# powerdist2.net
KiCad netlist of a schematic drawn in EAGLE
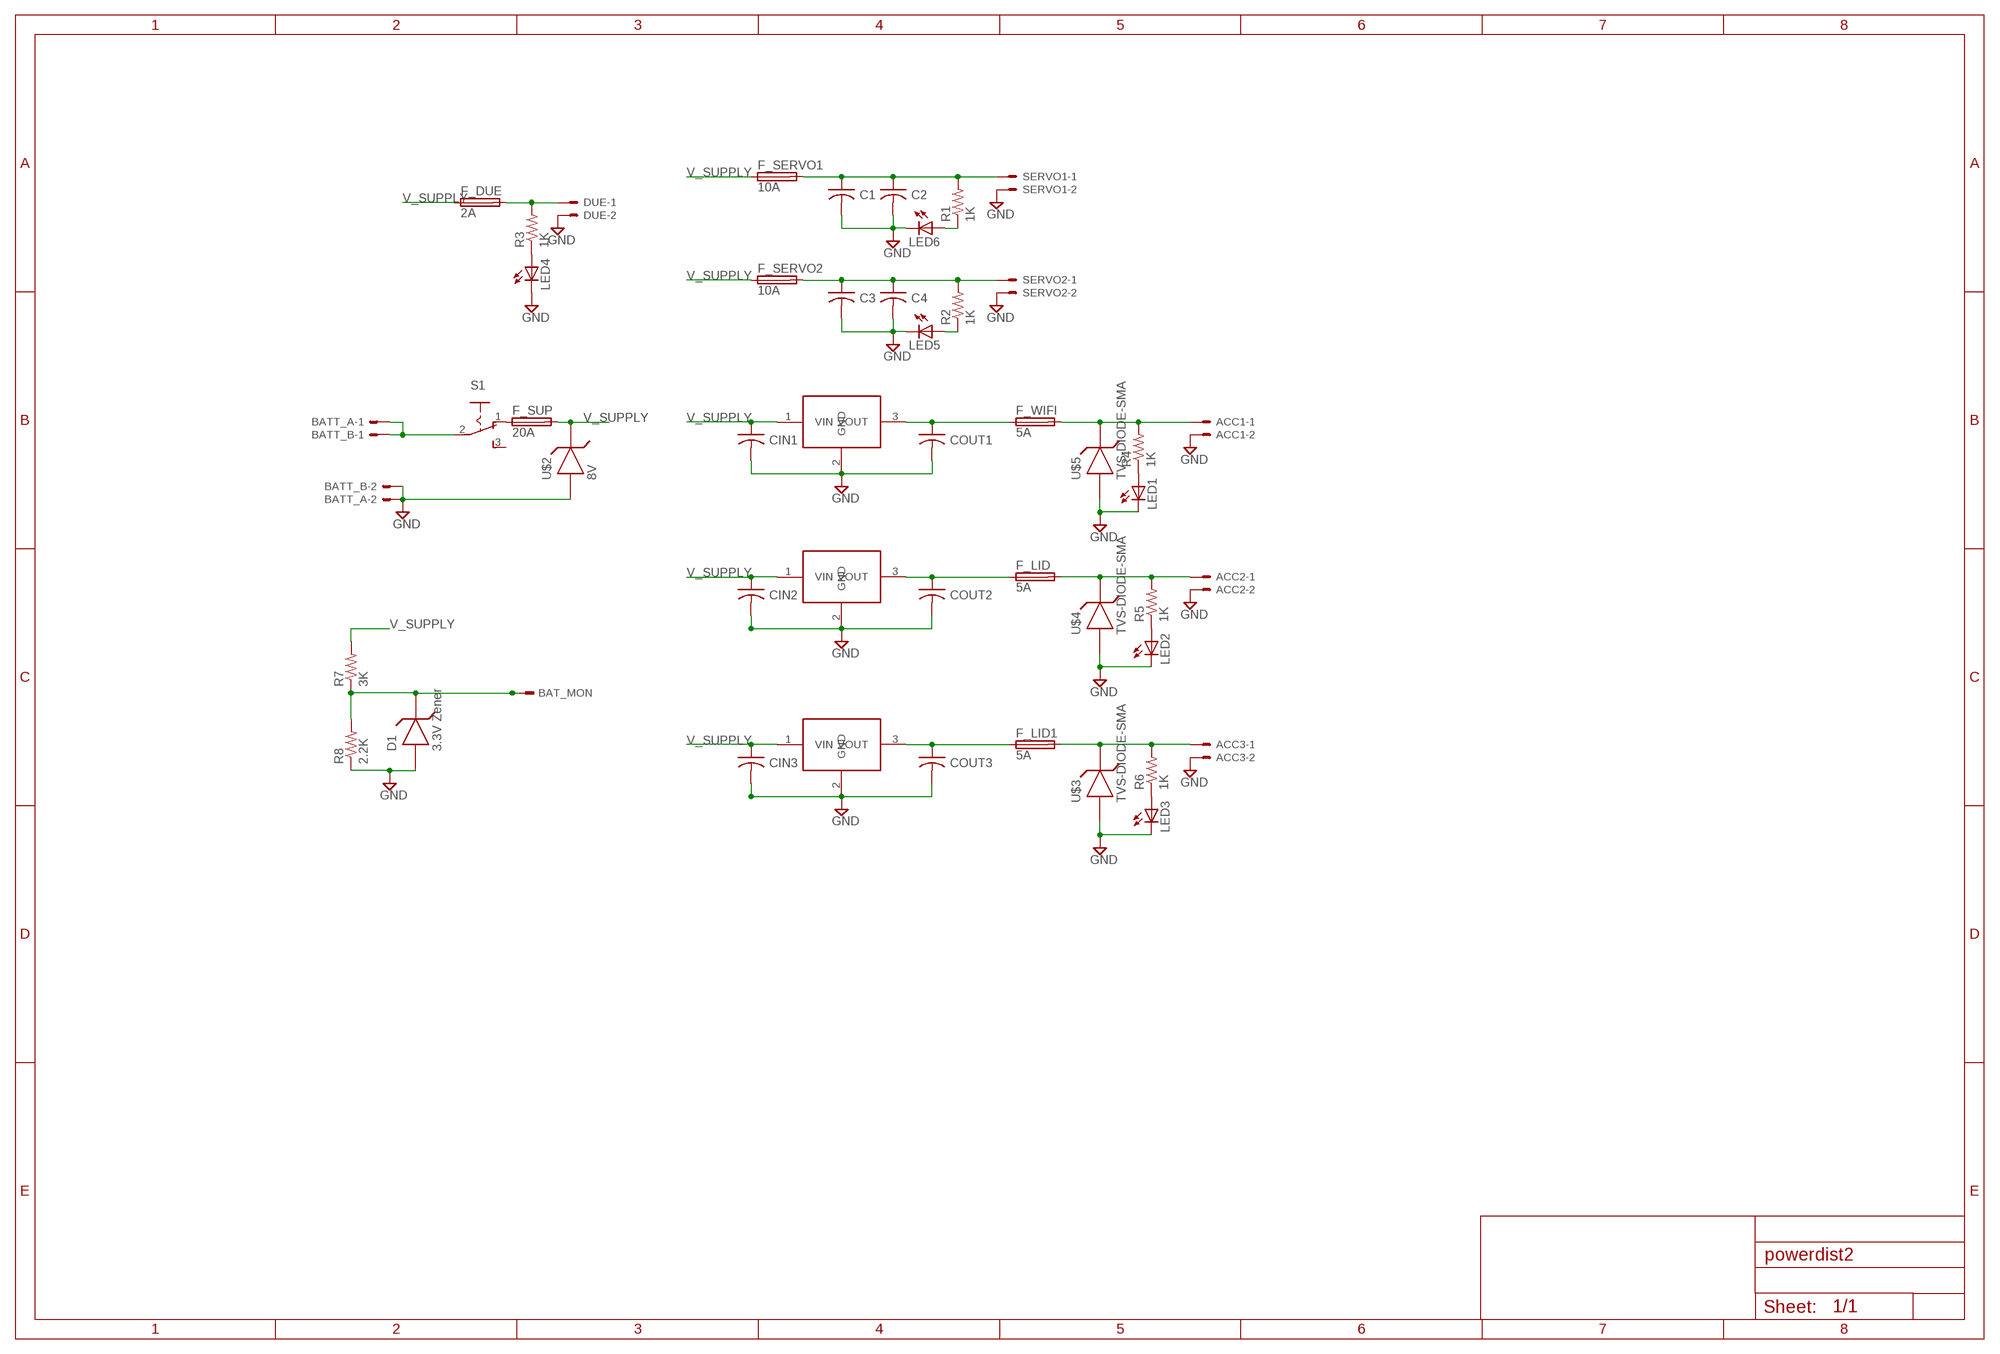
[diagram p0: schematic, sheet 1]

(export (version "E")
  (design (tool "Eeschema 10.0.6"))
  (components
    (comp (ref "ACC1")
      (value "C-GRID-02-70553")
      (footprint "eagle-import:70553-02")
      (libsource (lib "eagle-import") (part "C-GRID-02-70553"))
    )
    (comp (ref "ACC2")
      (value "5566-2")
      (footprint "eagle-import:5566-2")
      (libsource (lib "eagle-import") (part "5566-2"))
    )
    (comp (ref "ACC3")
      (value "5566-2")
      (footprint "eagle-import:5566-2")
      (libsource (lib "eagle-import") (part "5566-2"))
    )
    (comp (ref "BATT_A")
      (value "22-23-2021")
      (footprint "eagle-import:22-23-2021")
      (fields (field (name "MF") "MOLEX"))
      (libsource (lib "eagle-import") (part "22-23-2021"))
    )
    (comp (ref "BATT_B")
      (value "22-23-2021")
      (footprint "eagle-import:22-23-2021")
      (fields (field (name "MF") "MOLEX"))
      (libsource (lib "eagle-import") (part "22-23-2021"))
    )
    (comp (ref "BAT_MON")
      (value "TSW-101-02-S-S")
      (footprint "eagle-import:TSW-101-02-S-S")
      (libsource (lib "eagle-import") (part "TSW-101-02-S-S"))
    )
    (comp (ref "C1")
      (value "CAPACITORTH_CAP")
      (footprint "eagle-import:C025-025X050")
      (libsource (lib "eagle-import") (part "CAPACITORTH_CAP"))
    )
    (comp (ref "C2")
      (value "CAPACITORTH_CAP")
      (footprint "eagle-import:C025-025X050")
      (libsource (lib "eagle-import") (part "CAPACITORTH_CAP"))
    )
    (comp (ref "C3")
      (value "CAPACITORTH_CAP")
      (footprint "eagle-import:C025-025X050")
      (libsource (lib "eagle-import") (part "CAPACITORTH_CAP"))
    )
    (comp (ref "C4")
      (value "CAPACITORTH_CAP")
      (footprint "eagle-import:C025-025X050")
      (libsource (lib "eagle-import") (part "CAPACITORTH_CAP"))
    )
    (comp (ref "CIN1")
      (value "CAPACITORTH_CAP")
      (footprint "eagle-import:C025-025X050")
      (libsource (lib "eagle-import") (part "CAPACITORTH_CAP"))
    )
    (comp (ref "CIN2")
      (value "CAPACITORTH_CAP")
      (footprint "eagle-import:C025-025X050")
      (libsource (lib "eagle-import") (part "CAPACITORTH_CAP"))
    )
    (comp (ref "CIN3")
      (value "CAPACITORTH_CAP")
      (footprint "eagle-import:C025-025X050")
      (libsource (lib "eagle-import") (part "CAPACITORTH_CAP"))
    )
    (comp (ref "COUT1")
      (value "CAPACITORTH_CAP")
      (footprint "eagle-import:C025-025X050")
      (libsource (lib "eagle-import") (part "CAPACITORTH_CAP"))
    )
    (comp (ref "COUT2")
      (value "CAPACITORTH_CAP")
      (footprint "eagle-import:C025-025X050")
      (libsource (lib "eagle-import") (part "CAPACITORTH_CAP"))
    )
    (comp (ref "COUT3")
      (value "CAPACITORTH_CAP")
      (footprint "eagle-import:C025-025X050")
      (libsource (lib "eagle-import") (part "CAPACITORTH_CAP"))
    )
    (comp (ref "D1")
      (value "3.3V Zener")
      (footprint "eagle-import:SMA")
      (libsource (lib "eagle-import") (part "TVS-DIODE-SMA"))
    )
    (comp (ref "DUE")
      (value "C-GRID-02-70553")
      (footprint "eagle-import:70553-02")
      (libsource (lib "eagle-import") (part "C-GRID-02-70553"))
    )
    (comp (ref "F_DUE")
      (value "2A")
      (footprint "eagle-import:GSH15")
      (fields (field (name "MPN") "64900001039"))
      (libsource (lib "eagle-import") (part "GSH15"))
    )
    (comp (ref "F_LID")
      (value "5A")
      (footprint "eagle-import:GSH15")
      (fields (field (name "MPN") "64900001039"))
      (libsource (lib "eagle-import") (part "GSH15"))
    )
    (comp (ref "F_LID1")
      (value "5A")
      (footprint "eagle-import:GSH15")
      (fields (field (name "MPN") "64900001039"))
      (libsource (lib "eagle-import") (part "GSH15"))
    )
    (comp (ref "F_SERVO1")
      (value "10A")
      (footprint "eagle-import:GSH15")
      (fields (field (name "MPN") "64900001039"))
      (libsource (lib "eagle-import") (part "GSH15"))
    )
    (comp (ref "F_SERVO2")
      (value "10A")
      (footprint "eagle-import:GSH15")
      (fields (field (name "MPN") "64900001039"))
      (libsource (lib "eagle-import") (part "GSH15"))
    )
    (comp (ref "F_SUP")
      (value "20A")
      (footprint "eagle-import:GSH15")
      (fields (field (name "MPN") "64900001039"))
      (libsource (lib "eagle-import") (part "GSH15"))
    )
    (comp (ref "F_WIFI")
      (value "5A")
      (footprint "eagle-import:GSH15")
      (fields (field (name "MPN") "64900001039"))
      (libsource (lib "eagle-import") (part "GSH15"))
    )
    (comp (ref "LED1")
      (value "LEDCHIP-LED0805")
      (footprint "eagle-import:CHIP-LED0805")
      (libsource (lib "eagle-import") (part "LEDCHIP-LED0805"))
    )
    (comp (ref "LED2")
      (value "LEDCHIP-LED0805")
      (footprint "eagle-import:CHIP-LED0805")
      (libsource (lib "eagle-import") (part "LEDCHIP-LED0805"))
    )
    (comp (ref "LED3")
      (value "LEDCHIP-LED0805")
      (footprint "eagle-import:CHIP-LED0805")
      (libsource (lib "eagle-import") (part "LEDCHIP-LED0805"))
    )
    (comp (ref "LED4")
      (value "LEDCHIP-LED0805")
      (footprint "eagle-import:CHIP-LED0805")
      (libsource (lib "eagle-import") (part "LEDCHIP-LED0805"))
    )
    (comp (ref "LED5")
      (value "LEDCHIP-LED0805")
      (footprint "eagle-import:CHIP-LED0805")
      (libsource (lib "eagle-import") (part "LEDCHIP-LED0805"))
    )
    (comp (ref "LED6")
      (value "LEDCHIP-LED0805")
      (footprint "eagle-import:CHIP-LED0805")
      (libsource (lib "eagle-import") (part "LEDCHIP-LED0805"))
    )
    (comp (ref "R1")
      (value "1K")
      (footprint "eagle-import:0309_10")
      (libsource (lib "eagle-import") (part "R-US_0309/10"))
    )
    (comp (ref "R2")
      (value "1K")
      (footprint "eagle-import:0309_10")
      (libsource (lib "eagle-import") (part "R-US_0309/10"))
    )
    (comp (ref "R3")
      (value "1K")
      (footprint "eagle-import:0309_10")
      (libsource (lib "eagle-import") (part "R-US_0309/10"))
    )
    (comp (ref "R4")
      (value "1K")
      (footprint "eagle-import:0309_10")
      (libsource (lib "eagle-import") (part "R-US_0309/10"))
    )
    (comp (ref "R5")
      (value "1K")
      (footprint "eagle-import:0309_10")
      (libsource (lib "eagle-import") (part "R-US_0309/10"))
    )
    (comp (ref "R6")
      (value "1K")
      (footprint "eagle-import:0309_10")
      (libsource (lib "eagle-import") (part "R-US_0309/10"))
    )
    (comp (ref "R7")
      (value "3K")
      (footprint "eagle-import:0309_10")
      (libsource (lib "eagle-import") (part "R-US_0309/10"))
    )
    (comp (ref "R8")
      (value "2.2K")
      (footprint "eagle-import:0309_10")
      (libsource (lib "eagle-import") (part "R-US_0309/10"))
    )
    (comp (ref "S1")
      (value "255SB")
      (footprint "eagle-import:255SB")
      (libsource (lib "eagle-import") (part "255SB"))
    )
    (comp (ref "SERVO1")
      (value "5566-2")
      (footprint "eagle-import:5566-2")
      (libsource (lib "eagle-import") (part "5566-2"))
    )
    (comp (ref "SERVO2")
      (value "5566-2")
      (footprint "eagle-import:5566-2")
      (libsource (lib "eagle-import") (part "5566-2"))
    )
    (comp (ref "U$1")
      (value "MIC29150/29300/29500")
      (footprint "eagle-import:TO220")
      (libsource (lib "eagle-import") (part "MIC29150/29300/29500"))
    )
    (comp (ref "U$2")
      (value "8V")
      (footprint "eagle-import:SMA")
      (libsource (lib "eagle-import") (part "TVS-DIODE-SMA"))
    )
    (comp (ref "U$3")
      (value "TVS-DIODE-SMA")
      (footprint "eagle-import:SMA")
      (libsource (lib "eagle-import") (part "TVS-DIODE-SMA"))
    )
    (comp (ref "U$4")
      (value "TVS-DIODE-SMA")
      (footprint "eagle-import:SMA")
      (libsource (lib "eagle-import") (part "TVS-DIODE-SMA"))
    )
    (comp (ref "U$5")
      (value "TVS-DIODE-SMA")
      (footprint "eagle-import:SMA")
      (libsource (lib "eagle-import") (part "TVS-DIODE-SMA"))
    )
    (comp (ref "U$6")
      (value "MIC29150/29300/29500")
      (footprint "eagle-import:TO220")
      (libsource (lib "eagle-import") (part "MIC29150/29300/29500"))
    )
    (comp (ref "U$7")
      (value "MIC29150/29300/29500")
      (footprint "eagle-import:TO220")
      (libsource (lib "eagle-import") (part "MIC29150/29300/29500"))
    )
  )
  (nets
    (net (code "1") (name "/V_SUPPLY") (class "Default")
      (node (ref "CIN1") (pin "1") (pinfunction "1_1") (pintype "bidirectional"))
      (node (ref "CIN2") (pin "1") (pinfunction "1_1") (pintype "bidirectional"))
      (node (ref "CIN3") (pin "1") (pinfunction "1_1") (pintype "bidirectional"))
      (node (ref "F_DUE") (pin "1") (pinfunction "1_1") (pintype "passive"))
      (node (ref "F_SERVO1") (pin "1") (pinfunction "1_1") (pintype "passive"))
      (node (ref "F_SERVO2") (pin "1") (pinfunction "1_1") (pintype "passive"))
      (node (ref "F_SUP") (pin "2") (pinfunction "2_2") (pintype "passive"))
      (node (ref "R7") (pin "2") (pinfunction "2_2") (pintype "passive"))
      (node (ref "U$1") (pin "1") (pinfunction "VIN_1") (pintype "bidirectional"))
      (node (ref "U$2") (pin "CAT") (pinfunction "CAT_CAT") (pintype "bidirectional"))
      (node (ref "U$6") (pin "1") (pinfunction "VIN_1") (pintype "bidirectional"))
      (node (ref "U$7") (pin "1") (pinfunction "VIN_1") (pintype "bidirectional"))
    )
    (net (code "2") (name "GND") (class "Default")
      (node (ref "ACC1") (pin "2") (pinfunction "S_2") (pintype "passive"))
      (node (ref "ACC2") (pin "2") (pinfunction "S_2") (pintype "passive"))
      (node (ref "ACC3") (pin "2") (pinfunction "S_2") (pintype "passive"))
      (node (ref "BATT_A") (pin "2") (pinfunction "S_2") (pintype "passive"))
      (node (ref "BATT_B") (pin "2") (pinfunction "S_2") (pintype "passive"))
      (node (ref "C1") (pin "2") (pinfunction "2_2") (pintype "bidirectional"))
      (node (ref "C2") (pin "2") (pinfunction "2_2") (pintype "bidirectional"))
      (node (ref "C3") (pin "2") (pinfunction "2_2") (pintype "bidirectional"))
      (node (ref "C4") (pin "2") (pinfunction "2_2") (pintype "bidirectional"))
      (node (ref "CIN1") (pin "2") (pinfunction "2_2") (pintype "bidirectional"))
      (node (ref "CIN2") (pin "2") (pinfunction "2_2") (pintype "bidirectional"))
      (node (ref "CIN3") (pin "2") (pinfunction "2_2") (pintype "bidirectional"))
      (node (ref "COUT1") (pin "2") (pinfunction "2_2") (pintype "bidirectional"))
      (node (ref "COUT2") (pin "2") (pinfunction "2_2") (pintype "bidirectional"))
      (node (ref "COUT3") (pin "2") (pinfunction "2_2") (pintype "bidirectional"))
      (node (ref "D1") (pin "AN") (pinfunction "AN_AN") (pintype "bidirectional"))
      (node (ref "DUE") (pin "2") (pinfunction "S_2") (pintype "passive"))
      (node (ref "LED1") (pin "C") (pinfunction "C_C") (pintype "passive"))
      (node (ref "LED2") (pin "C") (pinfunction "C_C") (pintype "passive"))
      (node (ref "LED3") (pin "C") (pinfunction "C_C") (pintype "passive"))
      (node (ref "LED4") (pin "C") (pinfunction "C_C") (pintype "passive"))
      (node (ref "LED5") (pin "C") (pinfunction "C_C") (pintype "passive"))
      (node (ref "LED6") (pin "C") (pinfunction "C_C") (pintype "passive"))
      (node (ref "R8") (pin "1") (pinfunction "1_1") (pintype "passive"))
      (node (ref "SERVO1") (pin "2") (pinfunction "S_2") (pintype "passive"))
      (node (ref "SERVO2") (pin "2") (pinfunction "S_2") (pintype "passive"))
      (node (ref "U$1") (pin "2") (pinfunction "GND_2") (pintype "bidirectional"))
      (node (ref "U$2") (pin "AN") (pinfunction "AN_AN") (pintype "bidirectional"))
      (node (ref "U$3") (pin "AN") (pinfunction "AN_AN") (pintype "bidirectional"))
      (node (ref "U$4") (pin "AN") (pinfunction "AN_AN") (pintype "bidirectional"))
      (node (ref "U$5") (pin "AN") (pinfunction "AN_AN") (pintype "bidirectional"))
      (node (ref "U$6") (pin "2") (pinfunction "GND_2") (pintype "bidirectional"))
      (node (ref "U$7") (pin "2") (pinfunction "GND_2") (pintype "bidirectional"))
    )
    (net (code "3") (name "Net-(ACC1A-S)") (class "Default")
      (node (ref "ACC1") (pin "1") (pinfunction "S_1") (pintype "passive"))
      (node (ref "F_WIFI") (pin "2") (pinfunction "2_2") (pintype "passive"))
      (node (ref "R4") (pin "2") (pinfunction "2_2") (pintype "passive"))
      (node (ref "U$5") (pin "CAT") (pinfunction "CAT_CAT") (pintype "bidirectional"))
    )
    (net (code "4") (name "Net-(ACC2A-S)") (class "Default")
      (node (ref "ACC2") (pin "1") (pinfunction "S_1") (pintype "passive"))
      (node (ref "F_LID") (pin "2") (pinfunction "2_2") (pintype "passive"))
      (node (ref "R5") (pin "2") (pinfunction "2_2") (pintype "passive"))
      (node (ref "U$4") (pin "CAT") (pinfunction "CAT_CAT") (pintype "bidirectional"))
    )
    (net (code "5") (name "Net-(ACC3A-S)") (class "Default")
      (node (ref "ACC3") (pin "1") (pinfunction "S_1") (pintype "passive"))
      (node (ref "F_LID1") (pin "2") (pinfunction "2_2") (pintype "passive"))
      (node (ref "R6") (pin "2") (pinfunction "2_2") (pintype "passive"))
      (node (ref "U$3") (pin "CAT") (pinfunction "CAT_CAT") (pintype "bidirectional"))
    )
    (net (code "6") (name "Net-(BATT_AA-S)") (class "Default")
      (node (ref "BATT_A") (pin "1") (pinfunction "S_1") (pintype "passive"))
      (node (ref "BATT_B") (pin "1") (pinfunction "S_1") (pintype "passive"))
      (node (ref "S1") (pin "2") (pinfunction "P_2") (pintype "passive"))
    )
    (net (code "7") (name "Net-(BAT_MON-Pad1)") (class "Default")
      (node (ref "BAT_MON") (pin "1") (pinfunction "1_1") (pintype "passive"))
      (node (ref "D1") (pin "CAT") (pinfunction "CAT_CAT") (pintype "bidirectional"))
      (node (ref "R7") (pin "1") (pinfunction "1_1") (pintype "passive"))
      (node (ref "R8") (pin "2") (pinfunction "2_2") (pintype "passive"))
    )
    (net (code "8") (name "Net-(DUEA-S)") (class "Default")
      (node (ref "DUE") (pin "1") (pinfunction "S_1") (pintype "passive"))
      (node (ref "F_DUE") (pin "2") (pinfunction "2_2") (pintype "passive"))
      (node (ref "R3") (pin "2") (pinfunction "2_2") (pintype "passive"))
    )
    (net (code "9") (name "Net-(LED1-PadA)") (class "Default")
      (node (ref "LED1") (pin "A") (pinfunction "A_A") (pintype "passive"))
      (node (ref "R4") (pin "1") (pinfunction "1_1") (pintype "passive"))
    )
    (net (code "10") (name "Net-(LED2-PadA)") (class "Default")
      (node (ref "LED2") (pin "A") (pinfunction "A_A") (pintype "passive"))
      (node (ref "R5") (pin "1") (pinfunction "1_1") (pintype "passive"))
    )
    (net (code "11") (name "Net-(LED3-PadA)") (class "Default")
      (node (ref "LED3") (pin "A") (pinfunction "A_A") (pintype "passive"))
      (node (ref "R6") (pin "1") (pinfunction "1_1") (pintype "passive"))
    )
    (net (code "12") (name "Net-(LED4-PadA)") (class "Default")
      (node (ref "LED4") (pin "A") (pinfunction "A_A") (pintype "passive"))
      (node (ref "R3") (pin "1") (pinfunction "1_1") (pintype "passive"))
    )
    (net (code "13") (name "Net-(LED5-PadA)") (class "Default")
      (node (ref "LED5") (pin "A") (pinfunction "A_A") (pintype "passive"))
      (node (ref "R2") (pin "1") (pinfunction "1_1") (pintype "passive"))
    )
    (net (code "14") (name "Net-(LED6-PadA)") (class "Default")
      (node (ref "LED6") (pin "A") (pinfunction "A_A") (pintype "passive"))
      (node (ref "R1") (pin "1") (pinfunction "1_1") (pintype "passive"))
    )
    (net (code "15") (name "Net-(S1-O)") (class "Default")
      (node (ref "F_SUP") (pin "1") (pinfunction "1_1") (pintype "passive"))
      (node (ref "S1") (pin "1") (pinfunction "O_1") (pintype "passive"))
    )
    (net (code "16") (name "Net-(SERVO1A-S)") (class "Default")
      (node (ref "C1") (pin "1") (pinfunction "1_1") (pintype "bidirectional"))
      (node (ref "C2") (pin "1") (pinfunction "1_1") (pintype "bidirectional"))
      (node (ref "F_SERVO1") (pin "2") (pinfunction "2_2") (pintype "passive"))
      (node (ref "R1") (pin "2") (pinfunction "2_2") (pintype "passive"))
      (node (ref "SERVO1") (pin "1") (pinfunction "S_1") (pintype "passive"))
    )
    (net (code "17") (name "Net-(SERVO2A-S)") (class "Default")
      (node (ref "C3") (pin "1") (pinfunction "1_1") (pintype "bidirectional"))
      (node (ref "C4") (pin "1") (pinfunction "1_1") (pintype "bidirectional"))
      (node (ref "F_SERVO2") (pin "2") (pinfunction "2_2") (pintype "passive"))
      (node (ref "R2") (pin "2") (pinfunction "2_2") (pintype "passive"))
      (node (ref "SERVO2") (pin "1") (pinfunction "S_1") (pintype "passive"))
    )
    (net (code "18") (name "Net-(U$1-VOUT)") (class "Default")
      (node (ref "COUT3") (pin "1") (pinfunction "1_1") (pintype "bidirectional"))
      (node (ref "F_LID1") (pin "1") (pinfunction "1_1") (pintype "passive"))
      (node (ref "U$1") (pin "3") (pinfunction "VOUT_3") (pintype "bidirectional"))
    )
    (net (code "19") (name "Net-(U$6-VOUT)") (class "Default")
      (node (ref "COUT2") (pin "1") (pinfunction "1_1") (pintype "bidirectional"))
      (node (ref "F_LID") (pin "1") (pinfunction "1_1") (pintype "passive"))
      (node (ref "U$6") (pin "3") (pinfunction "VOUT_3") (pintype "bidirectional"))
    )
    (net (code "20") (name "Net-(U$7-VOUT)") (class "Default")
      (node (ref "COUT1") (pin "1") (pinfunction "1_1") (pintype "bidirectional"))
      (node (ref "F_WIFI") (pin "1") (pinfunction "1_1") (pintype "passive"))
      (node (ref "U$7") (pin "3") (pinfunction "VOUT_3") (pintype "bidirectional"))
    )
    (net (code "21") (name "unconnected-(S1-S-Pad3)") (class "Default")
      (node (ref "S1") (pin "3") (pinfunction "S_3") (pintype "passive"))
    )
  )
)
